# ATMega328.net
KiCad netlist of a schematic drawn in Altium Designer
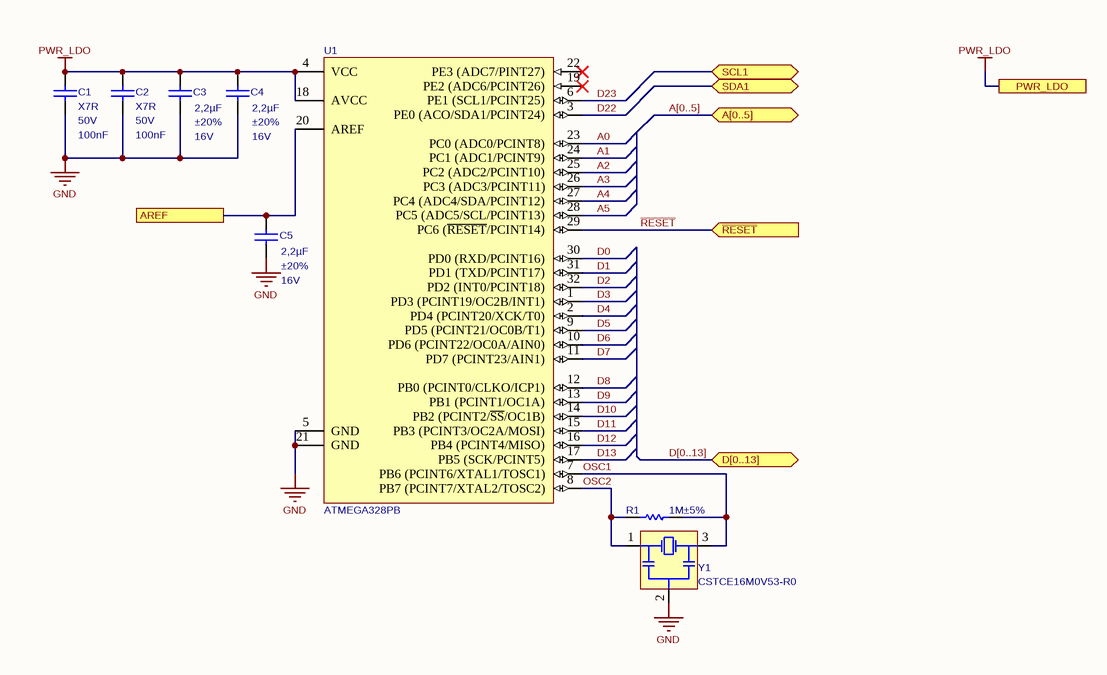
[diagram p0: ATMega328.SchDoc]

(export (version "E")
  (design (tool "Eeschema 10.0.6"))
  (components
    (comp (ref "C1")
      (value "C0603_100nF_50V_±10%_X7R")
      (footprint "C0603")
      (fields
        (field (name "DIELECTRIC") "X7R")
        (field (name "VOLTAGE") "50V")
        (field (name "CAPACITANCE") "100nF")
        (field (name "MANUFACTURER") "Kemet")
        (field (name "TOLERANCE") "±10%")
      )
      (libsource (lib "BQ Vault") (part "CMP-00257-1"))
    )
    (comp (ref "C2")
      (value "C0603_100nF_50V_±10%_X7R")
      (footprint "C0603")
      (fields
        (field (name "DIELECTRIC") "X7R")
        (field (name "VOLTAGE") "50V")
        (field (name "CAPACITANCE") "100nF")
        (field (name "MANUFACTURER") "Kemet")
        (field (name "TOLERANCE") "±10%")
      )
      (libsource (lib "BQ Vault") (part "CMP-00257-1"))
    )
    (comp (ref "C3")
      (value "C0402_2.2uF_16V_±20%")
      (footprint "C0402")
      (description "C0402_2.2uF_16V_±20%_X5R")
      (fields
        (field (name "VOLTAGE") "16V")
        (field (name "CAPACITANCE") "2,2µF")
        (field (name "PART NUMBER") "C0402_2.2uF_16V_±10%")
        (field (name "TOLERANCE") "±20%")
        (field (name "MANUFACTURER") "TDK")
      )
      (libsource (lib "BQ Vault") (part "Capacitor"))
    )
    (comp (ref "C4")
      (value "C0402_2.2uF_16V_±20%")
      (footprint "C0402")
      (description "C0402_2.2uF_16V_±20%_X5R")
      (fields
        (field (name "VOLTAGE") "16V")
        (field (name "CAPACITANCE") "2,2µF")
        (field (name "PART NUMBER") "C0402_2.2uF_16V_±10%")
        (field (name "TOLERANCE") "±20%")
        (field (name "MANUFACTURER") "TDK")
      )
      (libsource (lib "BQ Vault") (part "Capacitor"))
    )
    (comp (ref "C5")
      (value "C0402_2.2uF_16V_±20%")
      (footprint "C0402")
      (description "C0402_2.2uF_16V_±20%_X5R")
      (fields
        (field (name "VOLTAGE") "16V")
        (field (name "CAPACITANCE") "2,2µF")
        (field (name "PART NUMBER") "C0402_2.2uF_16V_±10%")
        (field (name "TOLERANCE") "±20%")
        (field (name "MANUFACTURER") "TDK")
      )
      (libsource (lib "BQ Vault") (part "Capacitor"))
    )
    (comp (ref "R1")
      (value "R0603_1M_0.1W_±5%")
      (footprint "R0603")
      (fields
        (field (name "TOLERANCE") "±5%")
        (field (name "POWER") "0.1W")
        (field (name "RESISTANCE") "1M")
        (field (name "MANUFACTURER") "Vishay")
      )
      (libsource (lib "BQ Vault") (part "Resistor"))
    )
    (comp (ref "U1")
      (value "ATMEGA328PB")
      (footprint "TQFP32")
      (description "8-bit Microcontrollers - MCU 32KB In-system Flash 20MHz 1.8V-5.5V")
      (fields (field (name "MANUFACTURER") "Atmel"))
      (libsource (lib "BQ Vault") (part "ATMEGA328PB"))
    )
    (comp (ref "Y1")
      (value "CSTCE16M0V53-R0")
      (footprint "Resonator_1.3x3.2")
      (description "Resonator 16MHz")
      (fields (field (name "MANUFACTURER") "Murata"))
      (libsource (lib "BQ Vault") (part "Resonator 3 pin"))
    )
  )
  (nets
    (net (code "1") (name "/A0") (class "Default")
      (node (ref "U1") (pin "23") (pinfunction "PC0_(ADC0/PCINT8)_23") (pintype "bidirectional"))
    )
    (net (code "2") (name "/A1") (class "Default")
      (node (ref "U1") (pin "24") (pinfunction "PC1_(ADC1/PCINT9)_24") (pintype "bidirectional"))
    )
    (net (code "3") (name "/A2") (class "Default")
      (node (ref "U1") (pin "25") (pinfunction "PC2_(ADC2/PCINT10)_25") (pintype "bidirectional"))
    )
    (net (code "4") (name "/A3") (class "Default")
      (node (ref "U1") (pin "26") (pinfunction "PC3_(ADC3/PCINT11)_26") (pintype "bidirectional"))
    )
    (net (code "5") (name "/A4") (class "Default")
      (node (ref "U1") (pin "27") (pinfunction "PC4_(ADC4/SDA/PCINT12)_27") (pintype "bidirectional"))
    )
    (net (code "6") (name "/A5") (class "Default")
      (node (ref "U1") (pin "28") (pinfunction "PC5_(ADC5/SCL/PCINT13)_28") (pintype "bidirectional"))
    )
    (net (code "7") (name "/AREF") (class "Default")
      (node (ref "C5") (pin "2") (pinfunction "2_2") (pintype "passive"))
      (node (ref "U1") (pin "20") (pinfunction "AREF_20") (pintype "passive"))
    )
    (net (code "9") (name "/D0") (class "Default")
      (node (ref "U1") (pin "30") (pinfunction "PD0_(RXD/PCINT16)_30") (pintype "bidirectional"))
    )
    (net (code "10") (name "/D1") (class "Default")
      (node (ref "U1") (pin "31") (pinfunction "PD1_(TXD/PCINT17)_31") (pintype "bidirectional"))
    )
    (net (code "11") (name "/D2") (class "Default")
      (node (ref "U1") (pin "32") (pinfunction "PD2_(INT0/PCINT18)_32") (pintype "bidirectional"))
    )
    (net (code "12") (name "/D3") (class "Default")
      (node (ref "U1") (pin "1") (pinfunction "PD3_(PCINT19/OC2B/INT1)_1") (pintype "bidirectional"))
    )
    (net (code "13") (name "/D4") (class "Default")
      (node (ref "U1") (pin "2") (pinfunction "PD4_(PCINT20/XCK/T0)_2") (pintype "bidirectional"))
    )
    (net (code "14") (name "/D5") (class "Default")
      (node (ref "U1") (pin "9") (pinfunction "PD5_(PCINT21/OC0B/T1)_9") (pintype "bidirectional"))
    )
    (net (code "15") (name "/D6") (class "Default")
      (node (ref "U1") (pin "10") (pinfunction "PD6_(PCINT22/OC0A/AIN0)_10") (pintype "bidirectional"))
    )
    (net (code "16") (name "/D7") (class "Default")
      (node (ref "U1") (pin "11") (pinfunction "PD7_(PCINT23/AIN1)_11") (pintype "bidirectional"))
    )
    (net (code "17") (name "/D8") (class "Default")
      (node (ref "U1") (pin "12") (pinfunction "PB0_(PCINT0/CLKO/ICP1)_12") (pintype "bidirectional"))
    )
    (net (code "18") (name "/D9") (class "Default")
      (node (ref "U1") (pin "13") (pinfunction "PB1_(PCINT1/OC1A)_13") (pintype "bidirectional"))
    )
    (net (code "19") (name "/D10") (class "Default")
      (node (ref "U1") (pin "14") (pinfunction "PB2_(PCINT2/~{SS}/OC1B)_14") (pintype "bidirectional"))
    )
    (net (code "20") (name "/D11") (class "Default")
      (node (ref "U1") (pin "15") (pinfunction "PB3_(PCINT3/OC2A/MOSI)_15") (pintype "bidirectional"))
    )
    (net (code "21") (name "/D12") (class "Default")
      (node (ref "U1") (pin "16") (pinfunction "PB4_(PCINT4/MISO)_16") (pintype "bidirectional"))
    )
    (net (code "22") (name "/D13") (class "Default")
      (node (ref "U1") (pin "17") (pinfunction "PB5_(SCK/PCINT5)_17") (pintype "bidirectional"))
    )
    (net (code "23") (name "/D22") (class "Default")
      (node (ref "U1") (pin "3") (pinfunction "PE0_(ACO/SDA1/PCINT24)_3") (pintype "bidirectional"))
    )
    (net (code "24") (name "/D23") (class "Default")
      (node (ref "U1") (pin "6") (pinfunction "PE1_(SCL1/PCINT25)_6") (pintype "bidirectional"))
    )
    (net (code "26") (name "/OSC1") (class "Default")
      (node (ref "R1") (pin "1") (pinfunction "1_1") (pintype "passive"))
      (node (ref "U1") (pin "7") (pinfunction "PB6_(PCINT6/XTAL1/TOSC1)_7") (pintype "bidirectional"))
      (node (ref "Y1") (pin "3") (pinfunction "OSC2_3") (pintype "passive"))
    )
    (net (code "27") (name "/OSC2") (class "Default")
      (node (ref "R1") (pin "2") (pinfunction "2_2") (pintype "passive"))
      (node (ref "U1") (pin "8") (pinfunction "PB7_(PCINT7/XTAL2/TOSC2)_8") (pintype "bidirectional"))
      (node (ref "Y1") (pin "1") (pinfunction "OSC1_1") (pintype "passive"))
    )
    (net (code "28") (name "/~{RESET}") (class "Default")
      (node (ref "U1") (pin "29") (pinfunction "PC6_(~{RESET}/PCINT14)_29") (pintype "bidirectional"))
    )
    (net (code "29") (name "GND") (class "Default")
      (node (ref "C1") (pin "1") (pinfunction "1_1") (pintype "passive"))
      (node (ref "C2") (pin "1") (pinfunction "1_1") (pintype "passive"))
      (node (ref "C3") (pin "1") (pinfunction "1_1") (pintype "passive"))
      (node (ref "C4") (pin "1") (pinfunction "1_1") (pintype "passive"))
      (node (ref "C5") (pin "1") (pinfunction "1_1") (pintype "passive"))
      (node (ref "U1") (pin "21") (pinfunction "GND_21") (pintype "power_in"))
      (node (ref "U1") (pin "5") (pinfunction "GND_5") (pintype "power_in"))
      (node (ref "Y1") (pin "2") (pinfunction "GND_2") (pintype "passive"))
    )
    (net (code "30") (name "PWR_LDO") (class "Default")
      (node (ref "C1") (pin "2") (pinfunction "2_2") (pintype "passive"))
      (node (ref "C2") (pin "2") (pinfunction "2_2") (pintype "passive"))
      (node (ref "C3") (pin "2") (pinfunction "2_2") (pintype "passive"))
      (node (ref "C4") (pin "2") (pinfunction "2_2") (pintype "passive"))
      (node (ref "U1") (pin "18") (pinfunction "AVCC_18") (pintype "power_in"))
      (node (ref "U1") (pin "4") (pinfunction "VCC_4") (pintype "power_in"))
    )
    (net (code "31") (name "unconnected-(U1-PE2_(ADC6{slash}PCINT26)-Pad19)") (class "Default")
      (node (ref "U1") (pin "19") (pinfunction "PE2_(ADC6/PCINT26)_19") (pintype "input+no_connect"))
    )
    (net (code "32") (name "unconnected-(U1-PE3_(ADC7{slash}PINT27)-Pad22)") (class "Default")
      (node (ref "U1") (pin "22") (pinfunction "PE3_(ADC7/PINT27)_22") (pintype "input+no_connect"))
    )
  )
)
